# gydrodrive_indication.net
KiCad netlist of a schematic drawn in Altium Designer
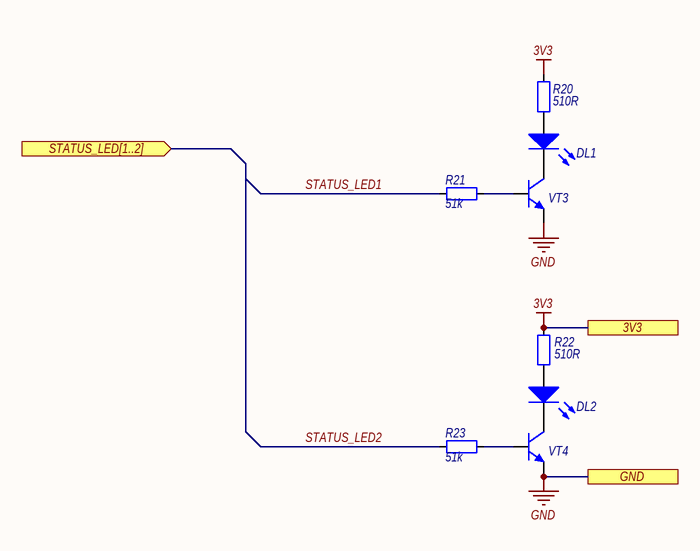
[diagram p0: gydrodrive_indication.SchDoc]

(export (version "E")
  (design (tool "Eeschema 10.0.6"))
  (components
    (comp (ref "DL1")
      (value "LED_0805")
      (footprint "LEDC2012-0805M")
      (description "Светодиод smd, корпус 0805")
      (libsource (lib "StdLib") (part "LED"))
    )
    (comp (ref "DL2")
      (value "LED_0805")
      (footprint "LEDC2012-0805M")
      (description "Светодиод smd, корпус 0805")
      (libsource (lib "StdLib") (part "LED"))
    )
    (comp (ref "R20")
      (value "RES_0805")
      (footprint "RESC2012-0805M")
      (description "Рез-р, корпус 0805")
      (fields
        (field (name "RESISTANCE") "510R")
        (field (name "PART NUMBER") "RESC_0805")
        (field (name "TOLERANCE") "5%")
      )
      (libsource (lib "") (part "RES_1"))
    )
    (comp (ref "R21")
      (value "RES_0805")
      (footprint "RESC2012-0805M")
      (description "Рез-р, корпус 0805")
      (fields
        (field (name "RESISTANCE") "51k")
        (field (name "PART NUMBER") "RESC_0805")
        (field (name "TOLERANCE") "5%")
      )
      (libsource (lib "StdLib") (part "RES"))
    )
    (comp (ref "R22")
      (value "RES_0805")
      (footprint "RESC2012-0805M")
      (description "Рез-р, корпус 0805")
      (fields
        (field (name "RESISTANCE") "510R")
        (field (name "PART NUMBER") "RESC_0805")
        (field (name "TOLERANCE") "5%")
      )
      (libsource (lib "") (part "RES_1"))
    )
    (comp (ref "R23")
      (value "RES_0805")
      (footprint "RESC2012-0805M")
      (description "Рез-р, корпус 0805")
      (fields
        (field (name "RESISTANCE") "51k")
        (field (name "PART NUMBER") "RESC_0805")
        (field (name "TOLERANCE") "5%")
      )
      (libsource (lib "StdLib") (part "RES"))
    )
    (comp (ref "VT3")
      (value "BC817")
      (footprint "SOT23-3M")
      (description "Биполярный транзистор")
      (fields (field (name "VOLTAGE") "45V"))
      (libsource (lib "StdLib") (part "BJT_NPN_SOT23"))
    )
    (comp (ref "VT4")
      (value "BC817")
      (footprint "SOT23-3M")
      (description "Биполярный транзистор")
      (fields (field (name "VOLTAGE") "45V"))
      (libsource (lib "StdLib") (part "BJT_NPN_SOT23"))
    )
  )
  (nets
    (net (code "1") (name "/STATUS_LED1") (class "Default")
      (node (ref "R21") (pin "2") (pinfunction "2_2") (pintype "passive"))
    )
    (net (code "2") (name "/STATUS_LED2") (class "Default")
      (node (ref "R23") (pin "2") (pinfunction "2_2") (pintype "passive"))
    )
    (net (code "4") (name "3V3") (class "Default")
      (node (ref "R20") (pin "1") (pinfunction "1_1") (pintype "passive"))
      (node (ref "R22") (pin "1") (pinfunction "1_1") (pintype "passive"))
    )
    (net (code "5") (name "GND") (class "Default")
      (node (ref "VT3") (pin "2") (pinfunction "E_2") (pintype "passive"))
      (node (ref "VT4") (pin "2") (pinfunction "E_2") (pintype "passive"))
    )
    (net (code "6") (name "Net-(DL1-A)") (class "Default")
      (node (ref "DL1") (pin "2") (pinfunction "A_2") (pintype "passive"))
      (node (ref "R20") (pin "2") (pinfunction "2_2") (pintype "passive"))
    )
    (net (code "7") (name "Net-(DL1-K)") (class "Default")
      (node (ref "DL1") (pin "1") (pinfunction "K_1") (pintype "passive"))
      (node (ref "VT3") (pin "3") (pinfunction "C_3") (pintype "passive"))
    )
    (net (code "8") (name "Net-(DL2-A)") (class "Default")
      (node (ref "DL2") (pin "2") (pinfunction "A_2") (pintype "passive"))
      (node (ref "R22") (pin "2") (pinfunction "2_2") (pintype "passive"))
    )
    (net (code "9") (name "Net-(DL2-K)") (class "Default")
      (node (ref "DL2") (pin "1") (pinfunction "K_1") (pintype "passive"))
      (node (ref "VT4") (pin "3") (pinfunction "C_3") (pintype "passive"))
    )
    (net (code "10") (name "Net-(VT3-B)") (class "Default")
      (node (ref "R21") (pin "1") (pinfunction "1_1") (pintype "passive"))
      (node (ref "VT3") (pin "1") (pinfunction "B_1") (pintype "passive"))
    )
    (net (code "11") (name "Net-(VT4-B)") (class "Default")
      (node (ref "R23") (pin "1") (pinfunction "1_1") (pintype "passive"))
      (node (ref "VT4") (pin "1") (pinfunction "B_1") (pintype "passive"))
    )
  )
)
